# rs485.net
KiCad netlist of a schematic drawn in Altium Designer
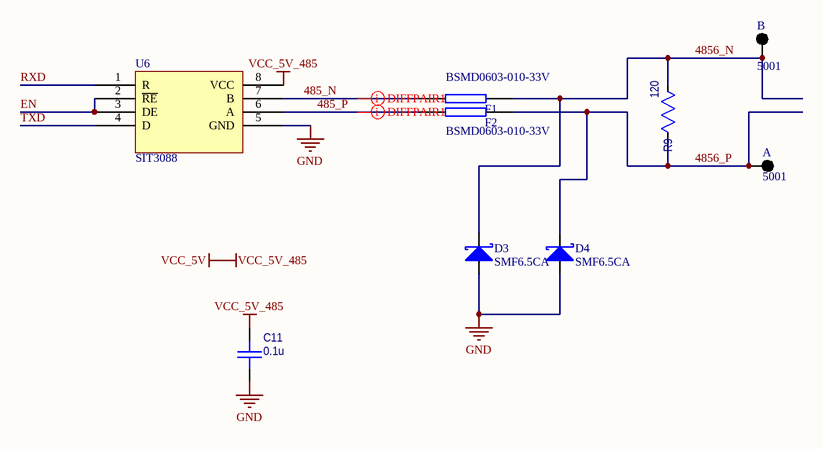
[diagram p0: rs485.SchDoc]

(export (version "E")
  (design (tool "Eeschema 10.0.6"))
  (components
    (comp (ref "A")
      (value "5001")
      (footprint "KSTN-5001")
      (description "Test Point, Black, 1-Pin THD, RoHS, Bulk")
      (fields (field (name "MANUFACTURER") "Keystone"))
      (libsource (lib "Bogen") (part "5001"))
    )
    (comp (ref "B")
      (value "5001")
      (footprint "KSTN-5001")
      (description "Test Point, Black, 1-Pin THD, RoHS, Bulk")
      (fields (field (name "MANUFACTURER") "Keystone"))
      (libsource (lib "Bogen") (part "5001"))
    )
    (comp (ref "C11")
      (value "0.1u")
      (footprint "CAPC1608X092N_0603")
      (description "Capacitor, MLCC")
      (fields (field (name "MANUFACTURER") "KEMET") (field (name "PARTNUMBER") "C0603C104M5RACTU"))
      (libsource (lib "Karl") (part "Capacitor_0603"))
    )
    (comp (ref "D3") (value "SMF6.5CA") (footprint "SOD123") (libsource (lib "*") (part "DIODE S")))
    (comp (ref "D4") (value "SMF6.5CA") (footprint "SOD123") (libsource (lib "*") (part "DIODE S")))
    (comp (ref "F1") (value "BSMD0603-010-33V") (footprint "0603R") (libsource (lib "*") (part "RES2")))
    (comp (ref "F2") (value "BSMD0603-010-33V") (footprint "0603R") (libsource (lib "*") (part "RES2")))
    (comp (ref "R9")
      (value "120")
      (footprint "RESC1608X055N_0603")
      (description "Resistor, Standard")
      (fields (field (name "MANUFACTURER") "Yageo") (field (name "PARTNUMBER") "RC0603FR-1075KL"))
      (libsource (lib "Karl") (part "Resistor_0603"))
    )
    (comp (ref "U6") (value "SIT3088") (footprint "so-8") (libsource (lib "Schlib1") (part "SN65HVD06D")))
  )
  (nets
    (net (code "1") (name "/485_N") (class "Default")
      (node (ref "F1") (pin "2") (pinfunction "2_2") (pintype "passive"))
      (node (ref "U6") (pin "7") (pinfunction "B_7") (pintype "passive"))
    )
    (net (code "2") (name "/485_P") (class "Default")
      (node (ref "F2") (pin "2") (pinfunction "2_2") (pintype "passive"))
      (node (ref "U6") (pin "6") (pinfunction "A_6") (pintype "passive"))
    )
    (net (code "3") (name "/4856_N") (class "Default")
      (node (ref "B") (pin "1") (pintype "passive"))
      (node (ref "D3") (pin "2") (pinfunction "K_2") (pintype "passive"))
      (node (ref "F1") (pin "1") (pinfunction "1_1") (pintype "passive"))
      (node (ref "R9") (pin "1") (pinfunction "1_1") (pintype "passive"))
    )
    (net (code "4") (name "/4856_P") (class "Default")
      (node (ref "A") (pin "1") (pintype "passive"))
      (node (ref "D4") (pin "2") (pinfunction "K_2") (pintype "passive"))
      (node (ref "F2") (pin "1") (pinfunction "1_1") (pintype "passive"))
      (node (ref "R9") (pin "2") (pinfunction "2_2") (pintype "passive"))
    )
    (net (code "5") (name "/EN") (class "Default")
      (node (ref "U6") (pin "2") (pinfunction "~{RE}_2") (pintype "passive"))
      (node (ref "U6") (pin "3") (pinfunction "DE_3") (pintype "passive"))
    )
    (net (code "6") (name "/RXD") (class "Default")
      (node (ref "U6") (pin "1") (pinfunction "R_1") (pintype "passive"))
    )
    (net (code "7") (name "/TXD") (class "Default")
      (node (ref "U6") (pin "4") (pinfunction "D_4") (pintype "passive"))
    )
    (net (code "8") (name "GND") (class "Default")
      (node (ref "C11") (pin "2") (pinfunction "2_2") (pintype "passive"))
      (node (ref "D3") (pin "1") (pinfunction "A_1") (pintype "passive"))
      (node (ref "D4") (pin "1") (pinfunction "A_1") (pintype "passive"))
      (node (ref "U6") (pin "5") (pinfunction "GND_5") (pintype "passive"))
    )
    (net (code "9") (name "VCC_5V") (class "Default")
      (node (ref "C11") (pin "1") (pinfunction "1_1") (pintype "passive"))
      (node (ref "U6") (pin "8") (pinfunction "VCC_8") (pintype "passive"))
    )
  )
)
